# 5v_Power_Supply.net
KiCad netlist of a schematic drawn in EAGLE
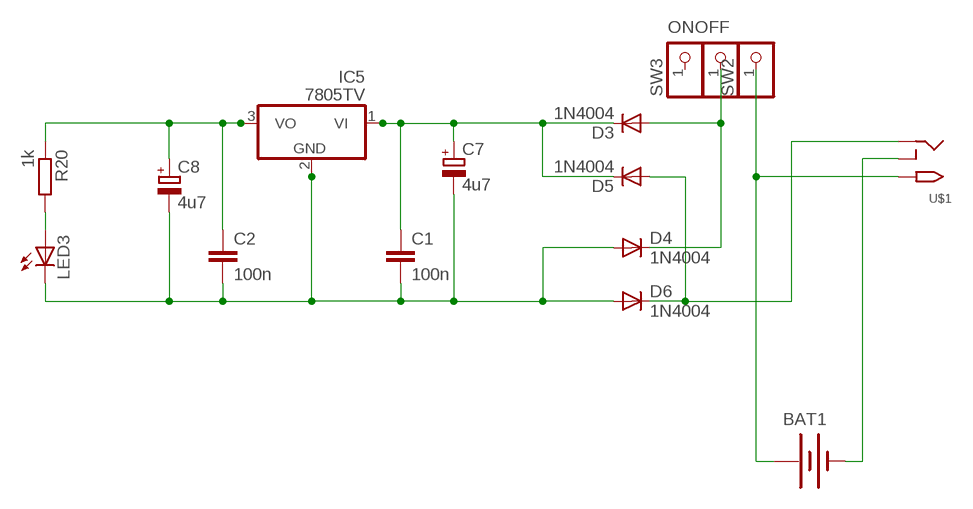
[diagram p0: schematic, sheet 1]

(export (version "E")
  (design (tool "Eeschema 10.0.6"))
  (components
    (comp (ref "BAT1")
      (value "BATTERY")
      (footprint "eagle-import:PP3_BATTERBOX")
      (libsource (lib "eagle-import") (part "BATTERY"))
    )
    (comp (ref "C1")
      (value "100n")
      (footprint "eagle-import:C025-024X044")
      (libsource (lib "eagle-import") (part "C-EU025-024X044"))
    )
    (comp (ref "C2")
      (value "100n")
      (footprint "eagle-import:C025-024X044")
      (libsource (lib "eagle-import") (part "C-EU025-024X044"))
    )
    (comp (ref "C7")
      (value "4u7")
      (footprint "eagle-import:E2,5-7")
      (libsource (lib "eagle-import") (part "CPOL-EUE2.5-7"))
    )
    (comp (ref "C8")
      (value "4u7")
      (footprint "eagle-import:E2,5-7")
      (libsource (lib "eagle-import") (part "CPOL-EUE2.5-7"))
    )
    (comp (ref "D3")
      (value "1N4004")
      (footprint "eagle-import:DO-VERT")
      (libsource (lib "eagle-import") (part "1N4004"))
    )
    (comp (ref "D4")
      (value "1N4004")
      (footprint "eagle-import:DO-VERT")
      (libsource (lib "eagle-import") (part "1N4004"))
    )
    (comp (ref "D5")
      (value "1N4004")
      (footprint "eagle-import:DO-VERT")
      (libsource (lib "eagle-import") (part "1N4004"))
    )
    (comp (ref "D6")
      (value "1N4004")
      (footprint "eagle-import:DO-VERT")
      (libsource (lib "eagle-import") (part "1N4004"))
    )
    (comp (ref "IC5")
      (value "7805TV")
      (footprint "eagle-import:TO220V")
      (libsource (lib "eagle-import") (part "78TV05"))
    )
    (comp (ref "LED3")
      (value "LED3MM")
      (footprint "eagle-import:LED3MM")
      (libsource (lib "eagle-import") (part "LED3MM"))
    )
    (comp (ref "ONOFF")
      (value "PINHD-1X1")
      (footprint "eagle-import:1X01")
      (libsource (lib "eagle-import") (part "PINHD-1X1"))
    )
    (comp (ref "R20")
      (value "1k")
      (footprint "eagle-import:0207_7")
      (libsource (lib "eagle-import") (part "R-EU_0207/7"))
    )
    (comp (ref "SW2")
      (value "PINHD-1X1")
      (footprint "eagle-import:1X01")
      (libsource (lib "eagle-import") (part "PINHD-1X1"))
    )
    (comp (ref "SW3")
      (value "PINHD-1X1")
      (footprint "eagle-import:1X01")
      (libsource (lib "eagle-import") (part "PINHD-1X1"))
    )
    (comp (ref "U$1")
      (value "2.1MMJACKTHM")
      (footprint "eagle-import:PJ-102A")
      (libsource (lib "eagle-import") (part "2.1MMJACKTHM"))
    )
  )
  (nets
    (net (code "1") (name "Net-(BAT1-+)") (class "Default")
      (node (ref "BAT1") (pin "9V") (pinfunction "+_9V") (pintype "power_in"))
      (node (ref "SW2") (pin "1") (pinfunction "1_1") (pintype "passive"))
      (node (ref "U$1") (pin "TIP") (pinfunction "TIP_TIP") (pintype "bidirectional"))
    )
    (net (code "2") (name "Net-(BAT1--)") (class "Default")
      (node (ref "BAT1") (pin "0V") (pinfunction "-_0V") (pintype "power_in"))
      (node (ref "U$1") (pin "RING_SW") (pinfunction "RING_SW_RING_SW") (pintype "bidirectional"))
    )
    (net (code "3") (name "Net-(D3-PadA)") (class "Default")
      (node (ref "D3") (pin "A") (pinfunction "A_A") (pintype "passive"))
      (node (ref "D4") (pin "C") (pinfunction "C_C") (pintype "passive"))
      (node (ref "ONOFF") (pin "1") (pinfunction "1_1") (pintype "passive"))
    )
    (net (code "4") (name "Net-(D5-PadA)") (class "Default")
      (node (ref "D5") (pin "A") (pinfunction "A_A") (pintype "passive"))
      (node (ref "D6") (pin "C") (pinfunction "C_C") (pintype "passive"))
      (node (ref "U$1") (pin "RING") (pinfunction "RING_RING") (pintype "bidirectional"))
    )
    (net (code "5") (name "Net-(IC5-GND)") (class "Default")
      (node (ref "C1") (pin "2") (pinfunction "2_2") (pintype "passive"))
      (node (ref "C2") (pin "2") (pinfunction "2_2") (pintype "passive"))
      (node (ref "C7") (pin "-") (pinfunction "-_-") (pintype "passive"))
      (node (ref "C8") (pin "-") (pinfunction "-_-") (pintype "passive"))
      (node (ref "D4") (pin "A") (pinfunction "A_A") (pintype "passive"))
      (node (ref "D6") (pin "A") (pinfunction "A_A") (pintype "passive"))
      (node (ref "IC5") (pin "2") (pinfunction "GND_2") (pintype "passive"))
      (node (ref "LED3") (pin "K") (pinfunction "C_K") (pintype "passive"))
    )
    (net (code "6") (name "Net-(IC5-VI)") (class "Default")
      (node (ref "C1") (pin "1") (pinfunction "1_1") (pintype "passive"))
      (node (ref "C7") (pin "+") (pinfunction "+_+") (pintype "passive"))
      (node (ref "D3") (pin "C") (pinfunction "C_C") (pintype "passive"))
      (node (ref "D5") (pin "C") (pinfunction "C_C") (pintype "passive"))
      (node (ref "IC5") (pin "1") (pinfunction "VI_1") (pintype "input"))
    )
    (net (code "7") (name "Net-(IC5-VO)") (class "Default")
      (node (ref "C2") (pin "1") (pinfunction "1_1") (pintype "passive"))
      (node (ref "C8") (pin "+") (pinfunction "+_+") (pintype "passive"))
      (node (ref "IC5") (pin "3") (pinfunction "VO_3") (pintype "passive"))
      (node (ref "R20") (pin "1") (pinfunction "1_1") (pintype "passive"))
    )
    (net (code "8") (name "Net-(LED3-PadA)") (class "Default")
      (node (ref "LED3") (pin "A") (pinfunction "A_A") (pintype "passive"))
      (node (ref "R20") (pin "2") (pinfunction "2_2") (pintype "passive"))
    )
    (net (code "9") (name "unconnected-(SW3-Pad1)") (class "Default")
      (node (ref "SW3") (pin "1") (pinfunction "1_1") (pintype "passive"))
    )
  )
)
